# SY8003ADFC.net
KiCad netlist of a schematic drawn in Altium Designer
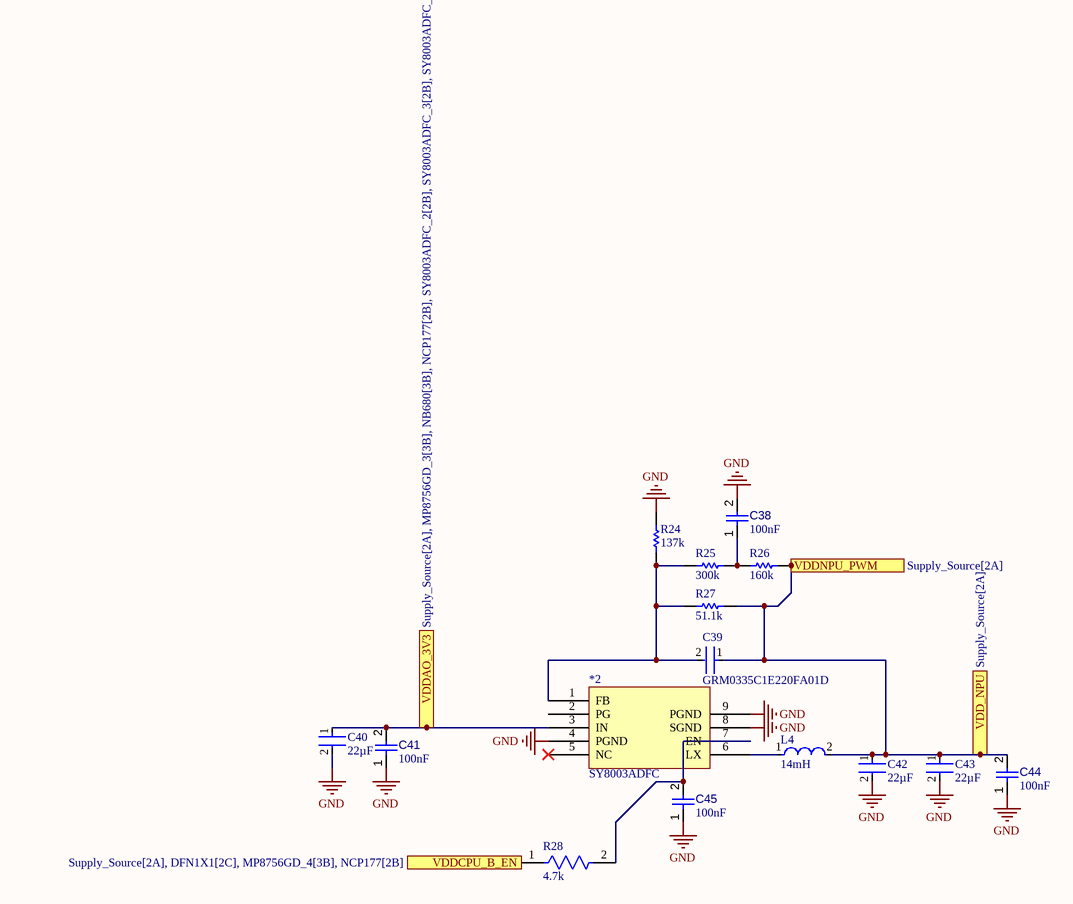
[diagram p0: SY8003ADFC.SchDoc]

(export (version "E")
  (design (tool "Eeschema 10.0.6"))
  (components
    (comp (ref "*2")
      (value "SY8003ADFC")
      (footprint "SON127P750X265-8N")
      (description "Switching Regulator, 3A, 1200kHz Switching Freq-Max, PDSO8")
      (libsource (lib "MIGUEL ANGEL ALVAREZ GUZMAN") (part "SY8003ADFC-Symbol-1"))
    )
    (comp (ref "C38")
      (value "100nF")
      (footprint "CAPC1005X56X25LL10T15")
      (description "Chip Capacitor, 0.1 uF, +/- 5%, 16 V, 0402 (1005 Metric)")
      (fields (field (name "TOLERANCE") "5%") (field (name "Comment") "Capacitor 0.1 uF +/- 5% 16 V 0402"))
      (libsource (lib "MIGUEL ANGEL ALVAREZ GUZMAN") (part "CAP-NP-2"))
    )
    (comp (ref "C39")
      (value "GRM0335C1E220FA01D")
      (footprint "FP-GRM033-0_03-IPC_C")
      (description "Chip Multilayer Ceramic Capacitors for General Purpose, 0201, 22pF, C0G, 30ppm/°C, 1%, 25V")
      (fields (field (name "TOLERANCE") "1%"))
      (libsource (lib "Altium Content Vault") (part "b4654b650e69147ec39a6b967a45e02"))
    )
    (comp (ref "C40")
      (value "22µF")
      (footprint "FP-GRM186-0_2-IPC_A")
      (description "6.3V 22uF X5R ±20% 0603 Multilayer Ceramic Capacitors MLCC - SMD/SMT ROHS")
      (fields (field (name "TOLERANCE") "20%") (field (name "Comment") "GRM186R60J226ME15D"))
      (libsource (lib "MIGUEL ANGEL ALVAREZ GUZMAN") (part "02cd4be3c70576c341d710602a673aa"))
    )
    (comp (ref "C41")
      (value "100nF")
      (footprint "CAPC1005X56X25LL10T15")
      (description "Chip Capacitor, 0.1 uF, +/- 5%, 16 V, 0402 (1005 Metric)")
      (fields (field (name "TOLERANCE") "5%") (field (name "Comment") "Capacitor 0.1 uF +/- 5% 16 V 0402"))
      (libsource (lib "MIGUEL ANGEL ALVAREZ GUZMAN") (part "CAP-NP-2"))
    )
    (comp (ref "C42")
      (value "22µF")
      (footprint "FP-GRM186-0_2-IPC_A")
      (description "6.3V 22uF X5R ±20% 0603 Multilayer Ceramic Capacitors MLCC - SMD/SMT ROHS")
      (fields (field (name "TOLERANCE") "20%") (field (name "Comment") "GRM186R60J226ME15D"))
      (libsource (lib "MIGUEL ANGEL ALVAREZ GUZMAN") (part "02cd4be3c70576c341d710602a673aa"))
    )
    (comp (ref "C43")
      (value "22µF")
      (footprint "FP-GRM186-0_2-IPC_A")
      (description "6.3V 22uF X5R ±20% 0603 Multilayer Ceramic Capacitors MLCC - SMD/SMT ROHS")
      (fields (field (name "TOLERANCE") "20%") (field (name "Comment") "GRM186R60J226ME15D"))
      (libsource (lib "MIGUEL ANGEL ALVAREZ GUZMAN") (part "02cd4be3c70576c341d710602a673aa"))
    )
    (comp (ref "C44")
      (value "100nF")
      (footprint "CAPC1005X56X25LL10T15")
      (description "Chip Capacitor, 0.1 uF, +/- 5%, 16 V, 0402 (1005 Metric)")
      (fields (field (name "TOLERANCE") "5%") (field (name "Comment") "Capacitor 0.1 uF +/- 5% 16 V 0402"))
      (libsource (lib "MIGUEL ANGEL ALVAREZ GUZMAN") (part "CAP-NP-2"))
    )
    (comp (ref "C45")
      (value "100nF")
      (footprint "CAPC1005X56X25LL10T15")
      (description "Chip Capacitor, 0.1 uF, +/- 5%, 16 V, 0402 (1005 Metric)")
      (fields (field (name "TOLERANCE") "5%") (field (name "Comment") "Capacitor 0.1 uF +/- 5% 16 V 0402"))
      (libsource (lib "MIGUEL ANGEL ALVAREZ GUZMAN") (part "CAP-NP-2"))
    )
    (comp (ref "L4")
      (value "14mH")
      (footprint "FP-IHLP-2525CZ-FP_2_413x3-MFG")
      (description "Inductor High Current Shielded Wirewound 1.5uH 20% 100KHz 9A 15mOhm DCR 2525 T/R")
      (fields (field (name "TOLERANCE") "20%") (field (name "Comment") "IHLP2525CZER1R5M01"))
      (libsource (lib "MIGUEL ANGEL ALVAREZ GUZMAN") (part "725321dda6339637d4d059423bc1c3c"))
    )
    (comp (ref "R24")
      (value "137k")
      (footprint "RESC0201(0603)_M")
      (description "CRCW FIXED RESISTOR 0201 (0603Metric) Chip Resistor ±1% ±100ppm/C 137kOhm 0.05W 1/20W")
      (fields (field (name "TOLERANCE") "1%") (field (name "Comment") "CRCW0201137KFKED"))
      (libsource (lib "MIGUEL ANGEL ALVAREZ GUZMAN") (part "RES"))
    )
    (comp (ref "R25")
      (value "300k")
      (footprint "RESC0201(0603)_M")
      (description "50mW Thick Film Resistors 25V ±1% ±200ppm/℃ 300kΩ 0201 Chip Resistor - Surface Mount ROHS")
      (fields (field (name "TOLERANCE") "1%") (field (name "Comment") "RC0201FR-07300KL"))
      (libsource (lib "MIGUEL ANGEL ALVAREZ GUZMAN") (part "RES"))
    )
    (comp (ref "R26")
      (value "160k")
      (footprint "RESC0603X28X15ML05T05")
      (description "CRCW Series 0201 160 kOhm ±1% 0.05 W ±200 ppm/K Thick Film Chip Resistor")
      (fields (field (name "TOLERANCE") "1%") (field (name "Comment") "CRCW0201160KFNED"))
      (libsource (lib "MIGUEL ANGEL ALVAREZ GUZMAN") (part "RES"))
    )
    (comp (ref "R27")
      (value "51.1k")
      (footprint "RESC0603X28X15ML05T05")
      (description "0201 51.1K ohms 1% 200PPM thick film surface mount chip resistor")
      (fields (field (name "TOLERANCE") "1%") (field (name "Comment") "CRCW020151K1FNED"))
      (libsource (lib "MIGUEL ANGEL ALVAREZ GUZMAN") (part "RES"))
    )
    (comp (ref "R28")
      (value "4.7k")
      (footprint "FP-RMCF0201-IPC_A")
      (description "Res Thick Film 0201 4.7K Ohm 5% 0.05W(1/20W) ±200ppm/C Pad SMD Automotive T/R")
      (fields (field (name "TOLERANCE") "5%") (field (name "Comment") "RMCF0201JT4K70"))
      (libsource (lib "MIGUEL ANGEL ALVAREZ GUZMAN") (part "1029c3af85768c4190bb7ad29bc67b5"))
    )
  )
  (nets
    (net (code "1") (name "/VDDAO_3V3") (class "Default")
      (node (ref "*2") (pin "3") (pinfunction "IN_3") (pintype "passive"))
      (node (ref "C40") (pin "1") (pinfunction "1_1") (pintype "passive"))
      (node (ref "C41") (pin "2") (pinfunction "2_2") (pintype "passive"))
    )
    (net (code "2") (name "/VDDCPU_B_EN") (class "Default")
      (node (ref "R28") (pin "1") (pinfunction "1_1") (pintype "passive"))
    )
    (net (code "3") (name "/VDDNPU_PWM") (class "Default")
      (node (ref "C39") (pin "1") (pinfunction "1_1") (pintype "passive"))
      (node (ref "C42") (pin "1") (pinfunction "1_1") (pintype "passive"))
      (node (ref "C43") (pin "1") (pinfunction "1_1") (pintype "passive"))
      (node (ref "C44") (pin "2") (pinfunction "2_2") (pintype "passive"))
      (node (ref "L4") (pin "2") (pinfunction "2_2") (pintype "passive"))
      (node (ref "R26") (pin "2") (pinfunction "2_2") (pintype "passive"))
      (node (ref "R27") (pin "2") (pinfunction "2_2") (pintype "passive"))
    )
    (net (code "4") (name "GND") (class "Default")
      (node (ref "*2") (pin "4") (pinfunction "PGND_4") (pintype "passive"))
      (node (ref "*2") (pin "8") (pinfunction "SGND_8") (pintype "passive"))
      (node (ref "*2") (pin "9") (pinfunction "PGND_9") (pintype "passive"))
      (node (ref "C38") (pin "2") (pinfunction "2_2") (pintype "passive"))
      (node (ref "C40") (pin "2") (pinfunction "2_2") (pintype "passive"))
      (node (ref "C41") (pin "1") (pinfunction "1_1") (pintype "passive"))
      (node (ref "C42") (pin "2") (pinfunction "2_2") (pintype "passive"))
      (node (ref "C43") (pin "2") (pinfunction "2_2") (pintype "passive"))
      (node (ref "C44") (pin "1") (pinfunction "1_1") (pintype "passive"))
      (node (ref "C45") (pin "1") (pinfunction "1_1") (pintype "passive"))
      (node (ref "R24") (pin "2") (pinfunction "2_2") (pintype "passive"))
    )
    (net (code "5") (name "Net-(*2-EN)") (class "Default")
      (node (ref "*2") (pin "7") (pinfunction "EN_7") (pintype "passive"))
      (node (ref "C45") (pin "2") (pinfunction "2_2") (pintype "passive"))
      (node (ref "R28") (pin "2") (pinfunction "2_2") (pintype "passive"))
    )
    (net (code "6") (name "Net-(*2-FB)") (class "Default")
      (node (ref "*2") (pin "1") (pinfunction "FB_1") (pintype "passive"))
      (node (ref "C39") (pin "2") (pinfunction "2_2") (pintype "passive"))
      (node (ref "R24") (pin "1") (pinfunction "1_1") (pintype "passive"))
      (node (ref "R25") (pin "1") (pinfunction "1_1") (pintype "passive"))
      (node (ref "R27") (pin "1") (pinfunction "1_1") (pintype "passive"))
    )
    (net (code "7") (name "Net-(*2-LX)") (class "Default")
      (node (ref "*2") (pin "6") (pinfunction "LX_6") (pintype "passive"))
      (node (ref "L4") (pin "1") (pinfunction "1_1") (pintype "passive"))
    )
    (net (code "8") (name "Net-(C38-Pad1)") (class "Default")
      (node (ref "C38") (pin "1") (pinfunction "1_1") (pintype "passive"))
      (node (ref "R25") (pin "2") (pinfunction "2_2") (pintype "passive"))
      (node (ref "R26") (pin "1") (pinfunction "1_1") (pintype "passive"))
    )
    (net (code "9") (name "unconnected-(*2-NC-Pad5)") (class "Default")
      (node (ref "*2") (pin "5") (pinfunction "NC_5") (pintype "passive+no_connect"))
    )
    (net (code "10") (name "unconnected-(*2-PG-Pad2)") (class "Default")
      (node (ref "*2") (pin "2") (pinfunction "PG_2") (pintype "passive"))
    )
  )
)
